# SensWear_Temperature.net
KiCad netlist of a schematic drawn in Altium Designer
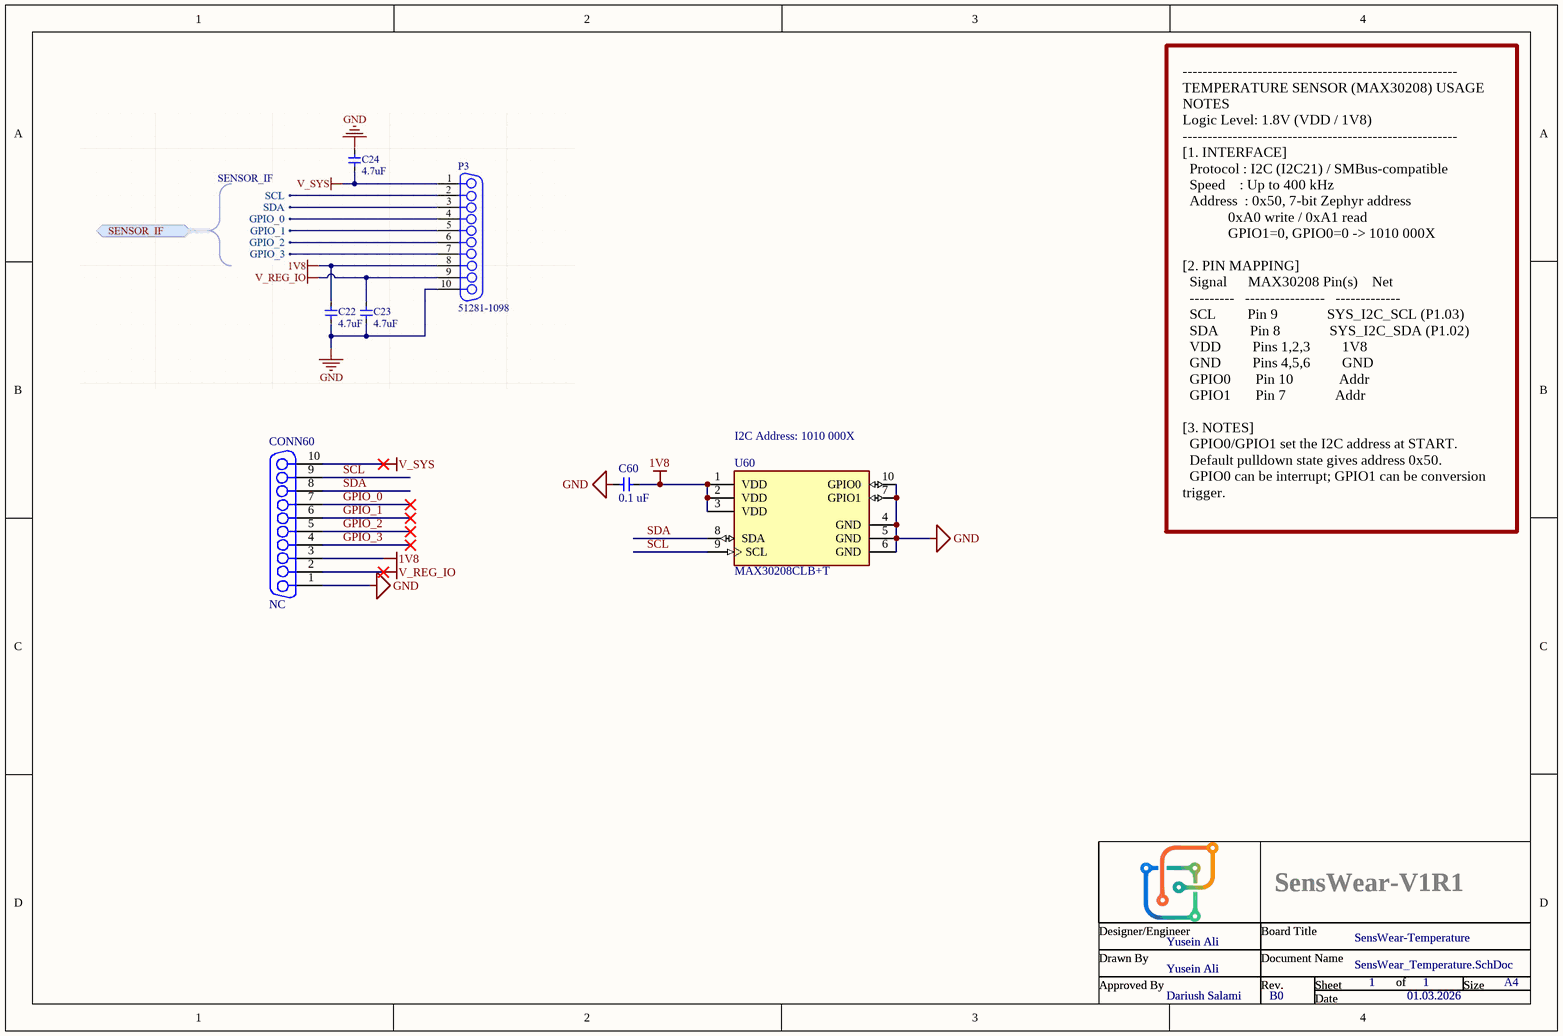
[diagram p0: SensWear_Temperature.SchDoc]

(export (version "E")
  (design (tool "Eeschema 10.0.6"))
  (components
    (comp (ref "C60")
      (value "0.1 uF")
      (footprint "CAPC1005X05N")
      (description "CAP CER 0.1UF 16V X5R 0402")
      (fields
        (field (name "MANUFACTURER") "Murata Electronics")
        (field (name "MANUFACTURER PART NUMBER") "GRM155R61C104KA88D")
      )
      (libsource (lib "SensWearComponents") (part "GRM155R61C104KA88D__2"))
    )
    (comp (ref "CONN60")
      (value "NC")
      (footprint "51281-1098-PCB")
      (libsource (lib "SensWearComponents") (part "51281-1098-PCB__2"))
    )
    (comp (ref "U60")
      (value "MAX30208CLB+T")
      (footprint "FP-L1022-2-MFG")
      (description "I2C Digital Temperature Sensor Serial I2C 10-Pin Thin LGA T/R")
      (fields (field (name "MANUFACTURER") "Maxim") (field (name "CHECKED") "FALSE"))
      (libsource (lib "SensWearComponents") (part "MAX30208CLB+T"))
    )
  )
  (nets
    (net (code "1") (name "/GPIO_0") (class "Default")
      (node (ref "CONN60") (pin "7") (pinfunction "7_7") (pintype "passive+no_connect"))
    )
    (net (code "2") (name "/GPIO_1") (class "Default")
      (node (ref "CONN60") (pin "6") (pinfunction "6_6") (pintype "passive+no_connect"))
    )
    (net (code "3") (name "/GPIO_2") (class "Default")
      (node (ref "CONN60") (pin "5") (pinfunction "5_5") (pintype "passive+no_connect"))
    )
    (net (code "4") (name "/GPIO_3") (class "Default")
      (node (ref "CONN60") (pin "4") (pinfunction "4_4") (pintype "passive+no_connect"))
    )
    (net (code "5") (name "/SCL") (class "Default")
      (node (ref "CONN60") (pin "9") (pinfunction "9_9") (pintype "passive"))
      (node (ref "U60") (pin "9") (pinfunction "SCL_9") (pintype "input"))
    )
    (net (code "6") (name "/SDA") (class "Default")
      (node (ref "CONN60") (pin "8") (pinfunction "8_8") (pintype "passive"))
      (node (ref "U60") (pin "8") (pinfunction "SDA_8") (pintype "bidirectional"))
    )
    (net (code "7") (name "1V8") (class "Default")
      (node (ref "C60") (pin "1") (pinfunction "1_1") (pintype "passive"))
      (node (ref "CONN60") (pin "3") (pinfunction "3_3") (pintype "passive"))
      (node (ref "U60") (pin "1") (pinfunction "VDD_1") (pintype "power_in"))
      (node (ref "U60") (pin "2") (pinfunction "VDD_2") (pintype "power_in"))
      (node (ref "U60") (pin "3") (pinfunction "VDD_3") (pintype "power_in"))
    )
    (net (code "8") (name "GND") (class "Default")
      (node (ref "C60") (pin "2") (pinfunction "2_2") (pintype "passive"))
      (node (ref "CONN60") (pin "1") (pinfunction "1_1") (pintype "passive"))
      (node (ref "U60") (pin "10") (pinfunction "GPIO0_10") (pintype "bidirectional"))
      (node (ref "U60") (pin "4") (pinfunction "GND_4") (pintype "power_in"))
      (node (ref "U60") (pin "5") (pinfunction "GND_5") (pintype "power_in"))
      (node (ref "U60") (pin "6") (pinfunction "GND_6") (pintype "power_in"))
      (node (ref "U60") (pin "7") (pinfunction "GPIO1_7") (pintype "bidirectional"))
    )
    (net (code "9") (name "V_REG_IO") (class "Default")
      (node (ref "CONN60") (pin "2") (pinfunction "2_2") (pintype "passive"))
    )
    (net (code "10") (name "V_SYS") (class "Default")
      (node (ref "CONN60") (pin "10") (pinfunction "10_10") (pintype "passive"))
    )
  )
)
